# maplemini.net
KiCad netlist of a schematic drawn in EAGLE
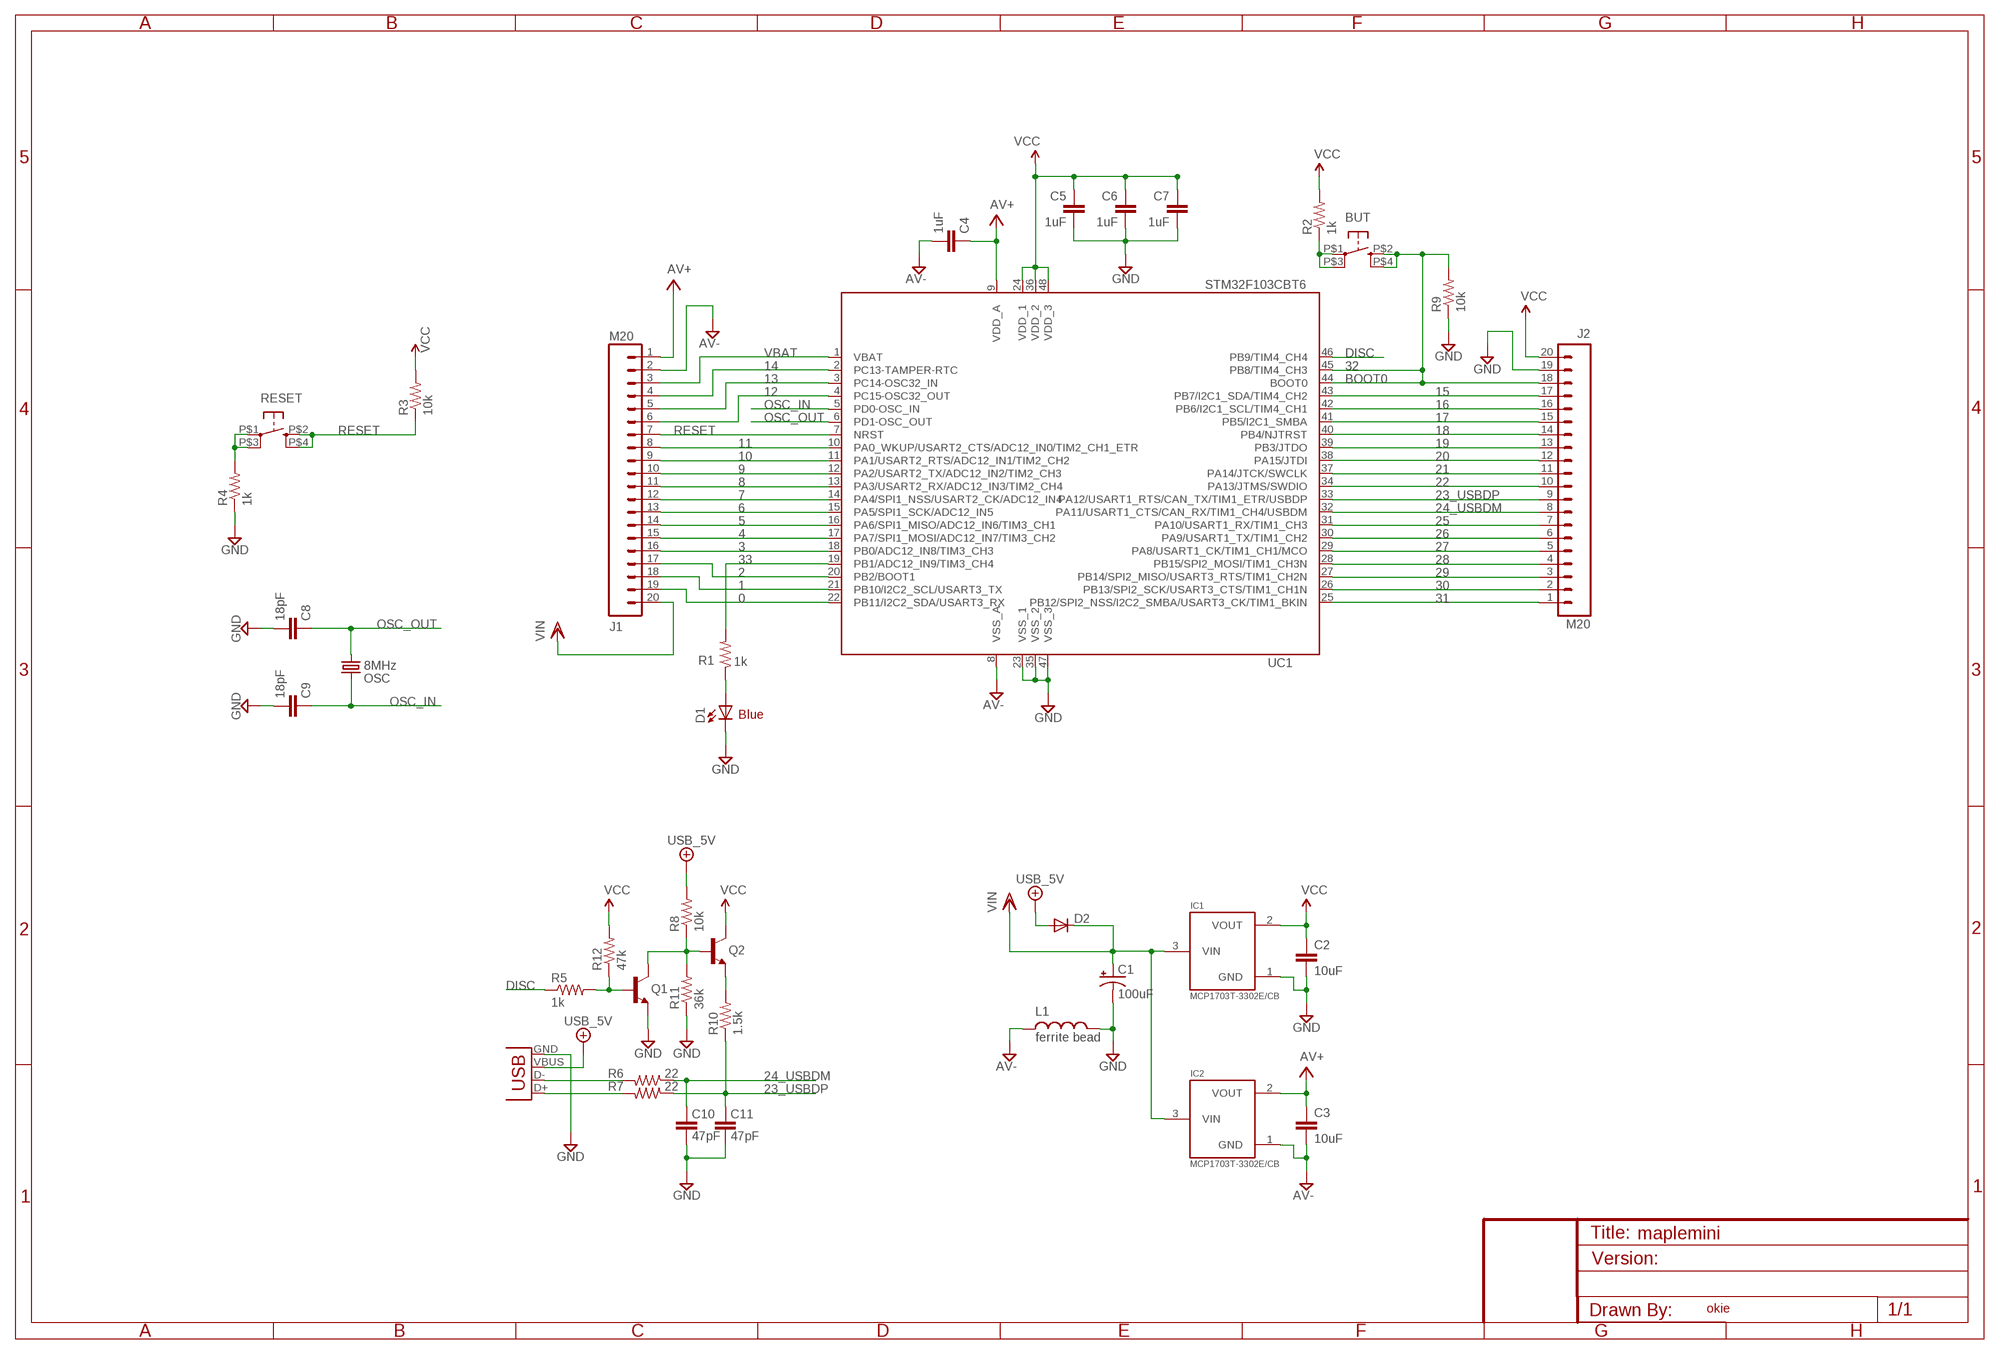
[diagram p0: schematic, sheet 1]

(export (version "E")
  (design (tool "Eeschema 10.0.6"))
  (components
    (comp (ref "BUT")
      (value "KMR211GLFS")
      (footprint "eagle-import:PUSHBUTTON-KMR241GLFS")
      (libsource (lib "eagle-import") (part "BUTTON-KMR241GLFS"))
    )
    (comp (ref "C1")
      (value "100uF")
      (footprint "eagle-import:EIA3216")
      (libsource (lib "eagle-import") (part "CAP_POL1206"))
    )
    (comp (ref "C2")
      (value "10uF")
      (footprint "eagle-import:0805")
      (libsource (lib "eagle-import") (part "SparkFun2_CAP0805"))
    )
    (comp (ref "C3")
      (value "10uF")
      (footprint "eagle-import:0805")
      (libsource (lib "eagle-import") (part "SparkFun2_CAP0805"))
    )
    (comp (ref "C4")
      (value "1uF")
      (footprint "eagle-import:C0402")
      (libsource (lib "eagle-import") (part "CAP0402"))
    )
    (comp (ref "C5")
      (value "1uF")
      (footprint "eagle-import:C0402")
      (libsource (lib "eagle-import") (part "CAP0402"))
    )
    (comp (ref "C6")
      (value "1uF")
      (footprint "eagle-import:C0402")
      (libsource (lib "eagle-import") (part "CAP0402"))
    )
    (comp (ref "C7")
      (value "1uF")
      (footprint "eagle-import:C0402")
      (libsource (lib "eagle-import") (part "CAP0402"))
    )
    (comp (ref "C8")
      (value "18pF")
      (footprint "eagle-import:C0402")
      (libsource (lib "eagle-import") (part "CAP0402"))
    )
    (comp (ref "C9")
      (value "18pF")
      (footprint "eagle-import:C0402")
      (libsource (lib "eagle-import") (part "CAP0402"))
    )
    (comp (ref "C10")
      (value "47pF")
      (footprint "eagle-import:C0402")
      (libsource (lib "eagle-import") (part "CAP0402"))
    )
    (comp (ref "C11")
      (value "47pF")
      (footprint "eagle-import:C0402")
      (libsource (lib "eagle-import") (part "CAP0402"))
    )
    (comp (ref "D1")
      (value "Blue")
      (footprint "eagle-import:LED-1206")
      (libsource (lib "eagle-import") (part "LED1206"))
    )
    (comp (ref "D2")
      (value "DIODESOD")
      (footprint "eagle-import:SOD-323")
      (libsource (lib "eagle-import") (part "DIODESOD"))
    )
    (comp (ref "IC1")
      (value "MCP1703T-3302E/CB")
      (footprint "eagle-import:SOT23")
      (libsource (lib "eagle-import") (part "MCP1700T"))
    )
    (comp (ref "IC2")
      (value "MCP1703T-3302E/CB")
      (footprint "eagle-import:SOT23")
      (libsource (lib "eagle-import") (part "MCP1700T"))
    )
    (comp (ref "J1")
      (value "M20")
      (footprint "eagle-import:1X20")
      (libsource (lib "eagle-import") (part "M20"))
    )
    (comp (ref "J2")
      (value "M20")
      (footprint "eagle-import:1X20")
      (libsource (lib "eagle-import") (part "M20"))
    )
    (comp (ref "L1")
      (value "ferrite bead")
      (footprint "eagle-import:0603")
      (libsource (lib "eagle-import") (part "INDUCTOR0603"))
    )
    (comp (ref "OSC")
      (value "8MHz")
      (footprint "eagle-import:CRYSTAL-SMD-5X3")
      (libsource (lib "eagle-import") (part "CRYSTAL5X3"))
    )
    (comp (ref "Q1")
      (value "NPN-BJT")
      (footprint "eagle-import:SOT23")
      (libsource (lib "eagle-import") (part "TRANSISTOR_NPNSOT23"))
    )
    (comp (ref "Q2")
      (value "NPN-BJT")
      (footprint "eagle-import:SOT23")
      (libsource (lib "eagle-import") (part "TRANSISTOR_NPNSOT23"))
    )
    (comp (ref "R1")
      (value "1k")
      (footprint "eagle-import:C0402")
      (libsource (lib "eagle-import") (part "RESISTOR0402"))
    )
    (comp (ref "R2")
      (value "1k")
      (footprint "eagle-import:C0402")
      (libsource (lib "eagle-import") (part "RESISTOR0402"))
    )
    (comp (ref "R3")
      (value "10k")
      (footprint "eagle-import:C0402")
      (libsource (lib "eagle-import") (part "RESISTOR0402"))
    )
    (comp (ref "R4")
      (value "1k")
      (footprint "eagle-import:C0402")
      (libsource (lib "eagle-import") (part "RESISTOR0402"))
    )
    (comp (ref "R5")
      (value "1k")
      (footprint "eagle-import:C0402")
      (libsource (lib "eagle-import") (part "RESISTOR0402"))
    )
    (comp (ref "R6")
      (value "22")
      (footprint "eagle-import:C0402")
      (libsource (lib "eagle-import") (part "RESISTOR0402"))
    )
    (comp (ref "R7")
      (value "22")
      (footprint "eagle-import:C0402")
      (libsource (lib "eagle-import") (part "RESISTOR0402"))
    )
    (comp (ref "R8")
      (value "10k")
      (footprint "eagle-import:C0402")
      (libsource (lib "eagle-import") (part "RESISTOR0402"))
    )
    (comp (ref "R9")
      (value "10k")
      (footprint "eagle-import:C0402")
      (libsource (lib "eagle-import") (part "RESISTOR0402"))
    )
    (comp (ref "R10")
      (value "1.5k")
      (footprint "eagle-import:C0402")
      (libsource (lib "eagle-import") (part "RESISTOR0402"))
    )
    (comp (ref "R11")
      (value "36k")
      (footprint "eagle-import:C0402")
      (libsource (lib "eagle-import") (part "RESISTOR0402"))
    )
    (comp (ref "R12")
      (value "47k")
      (footprint "eagle-import:C0402")
      (libsource (lib "eagle-import") (part "RESISTOR0402"))
    )
    (comp (ref "RESET")
      (value "KMR211GLFS")
      (footprint "eagle-import:PUSHBUTTON-KMR241GLFS")
      (libsource (lib "eagle-import") (part "BUTTON-KMR241GLFS"))
    )
    (comp (ref "UC1")
      (value "STM32F103CBT6")
      (footprint "eagle-import:LQFP48")
      (libsource (lib "eagle-import") (part "STM32F103CB"))
    )
    (comp (ref "X1")
      (value "USB-MINIB")
      (footprint "eagle-import:USB-MINIB")
      (libsource (lib "eagle-import") (part "USBSMD"))
    )
  )
  (nets
    (net (code "1") (name "/0") (class "Default")
      (node (ref "J1") (pin "19") (pinfunction "19_19") (pintype "passive"))
      (node (ref "UC1") (pin "22") (pinfunction "PB11/I2C2_SDA/USART3_RX_22") (pintype "input"))
    )
    (net (code "2") (name "/1") (class "Default")
      (node (ref "J1") (pin "18") (pinfunction "18_18") (pintype "passive"))
      (node (ref "UC1") (pin "21") (pinfunction "PB10/I2C2_SCL/USART3_TX_21") (pintype "input"))
    )
    (net (code "3") (name "/2") (class "Default")
      (node (ref "J1") (pin "17") (pinfunction "17_17") (pintype "passive"))
      (node (ref "UC1") (pin "20") (pinfunction "PB2/BOOT1_20") (pintype "bidirectional"))
    )
    (net (code "4") (name "/3") (class "Default")
      (node (ref "J1") (pin "16") (pinfunction "16_16") (pintype "passive"))
      (node (ref "UC1") (pin "18") (pinfunction "PB0/ADC12_IN8/TIM3_CH3_18") (pintype "bidirectional"))
    )
    (net (code "5") (name "/4") (class "Default")
      (node (ref "J1") (pin "15") (pinfunction "15_15") (pintype "passive"))
      (node (ref "UC1") (pin "17") (pinfunction "PA7/SPI1_MOSI/ADC12_IN7/TIM3_CH2_17") (pintype "bidirectional"))
    )
    (net (code "6") (name "/5") (class "Default")
      (node (ref "J1") (pin "14") (pinfunction "14_14") (pintype "passive"))
      (node (ref "UC1") (pin "16") (pinfunction "PA6/SPI1_MISO/ADC12_IN6/TIM3_CH1_16") (pintype "bidirectional"))
    )
    (net (code "7") (name "/6") (class "Default")
      (node (ref "J1") (pin "13") (pinfunction "13_13") (pintype "passive"))
      (node (ref "UC1") (pin "15") (pinfunction "PA5/SPI1_SCK/ADC12_IN5_15") (pintype "bidirectional"))
    )
    (net (code "8") (name "/7") (class "Default")
      (node (ref "J1") (pin "12") (pinfunction "12_12") (pintype "passive"))
      (node (ref "UC1") (pin "14") (pinfunction "PA4/SPI1_NSS/USART2_CK/ADC12_IN4_14") (pintype "bidirectional"))
    )
    (net (code "9") (name "/8") (class "Default")
      (node (ref "J1") (pin "11") (pinfunction "11_11") (pintype "passive"))
      (node (ref "UC1") (pin "13") (pinfunction "PA3/USART2_RX/ADC12_IN3/TIM2_CH4_13") (pintype "bidirectional"))
    )
    (net (code "10") (name "/9") (class "Default")
      (node (ref "J1") (pin "10") (pinfunction "10_10") (pintype "passive"))
      (node (ref "UC1") (pin "12") (pinfunction "PA2/USART2_TX/ADC12_IN2/TIM2_CH3_12") (pintype "bidirectional"))
    )
    (net (code "11") (name "/10") (class "Default")
      (node (ref "J1") (pin "9") (pinfunction "9_9") (pintype "passive"))
      (node (ref "UC1") (pin "11") (pinfunction "PA1/USART2_RTS/ADC12_IN1/TIM2_CH2_11") (pintype "bidirectional"))
    )
    (net (code "12") (name "/11") (class "Default")
      (node (ref "J1") (pin "8") (pinfunction "8_8") (pintype "passive"))
      (node (ref "UC1") (pin "10") (pinfunction "PA0_WKUP/USART2_CTS/ADC12_IN0/TIM2_CH1_ETR_10") (pintype "bidirectional"))
    )
    (net (code "13") (name "/12") (class "Default")
      (node (ref "J1") (pin "6") (pinfunction "6_6") (pintype "passive"))
      (node (ref "UC1") (pin "4") (pinfunction "PC15-OSC32_OUT_4") (pintype "input"))
    )
    (net (code "14") (name "/13") (class "Default")
      (node (ref "J1") (pin "5") (pinfunction "5_5") (pintype "passive"))
      (node (ref "UC1") (pin "3") (pinfunction "PC14-OSC32_IN_3") (pintype "input"))
    )
    (net (code "15") (name "/14") (class "Default")
      (node (ref "J1") (pin "4") (pinfunction "4_4") (pintype "passive"))
      (node (ref "UC1") (pin "2") (pinfunction "PC13-TAMPER-RTC_2") (pintype "input"))
    )
    (net (code "16") (name "/15") (class "Default")
      (node (ref "J2") (pin "17") (pinfunction "17_17") (pintype "passive"))
      (node (ref "UC1") (pin "43") (pinfunction "PB7/I2C1_SDA/TIM4_CH2_43") (pintype "bidirectional"))
    )
    (net (code "17") (name "/16") (class "Default")
      (node (ref "J2") (pin "16") (pinfunction "16_16") (pintype "passive"))
      (node (ref "UC1") (pin "42") (pinfunction "PB6/I2C1_SCL/TIM4_CH1_42") (pintype "input"))
    )
    (net (code "18") (name "/17") (class "Default")
      (node (ref "J2") (pin "15") (pinfunction "15_15") (pintype "passive"))
      (node (ref "UC1") (pin "41") (pinfunction "PB5/I2C1_SMBA_41") (pintype "input"))
    )
    (net (code "19") (name "/18") (class "Default")
      (node (ref "J2") (pin "14") (pinfunction "14_14") (pintype "passive"))
      (node (ref "UC1") (pin "40") (pinfunction "PB4/NJTRST_40") (pintype "bidirectional"))
    )
    (net (code "20") (name "/19") (class "Default")
      (node (ref "J2") (pin "13") (pinfunction "13_13") (pintype "passive"))
      (node (ref "UC1") (pin "39") (pinfunction "PB3/JTDO_39") (pintype "bidirectional"))
    )
    (net (code "21") (name "/20") (class "Default")
      (node (ref "J2") (pin "12") (pinfunction "12_12") (pintype "passive"))
      (node (ref "UC1") (pin "38") (pinfunction "PA15/JTDI_38") (pintype "bidirectional"))
    )
    (net (code "22") (name "/21") (class "Default")
      (node (ref "J2") (pin "11") (pinfunction "11_11") (pintype "passive"))
      (node (ref "UC1") (pin "37") (pinfunction "PA14/JTCK/SWCLK_37") (pintype "bidirectional"))
    )
    (net (code "23") (name "/22") (class "Default")
      (node (ref "J2") (pin "10") (pinfunction "10_10") (pintype "passive"))
      (node (ref "UC1") (pin "34") (pinfunction "PA13/JTMS/SWDIO_34") (pintype "bidirectional"))
    )
    (net (code "24") (name "/23_USBDP") (class "Default")
      (node (ref "C11") (pin "2") (pinfunction "2_2") (pintype "passive"))
      (node (ref "J2") (pin "9") (pinfunction "9_9") (pintype "passive"))
      (node (ref "R10") (pin "1") (pinfunction "1_1") (pintype "passive"))
      (node (ref "R7") (pin "1") (pinfunction "1_1") (pintype "passive"))
      (node (ref "UC1") (pin "33") (pinfunction "PA12/USART1_RTS/CAN_TX/TIM1_ETR/USBDP_33") (pintype "bidirectional"))
    )
    (net (code "25") (name "/24_USBDM") (class "Default")
      (node (ref "C10") (pin "2") (pinfunction "2_2") (pintype "passive"))
      (node (ref "J2") (pin "8") (pinfunction "8_8") (pintype "passive"))
      (node (ref "R6") (pin "1") (pinfunction "1_1") (pintype "passive"))
      (node (ref "UC1") (pin "32") (pinfunction "PA11/USART1_CTS/CAN_RX/TIM1_CH4/USBDM_32") (pintype "bidirectional"))
    )
    (net (code "26") (name "/25") (class "Default")
      (node (ref "J2") (pin "7") (pinfunction "7_7") (pintype "passive"))
      (node (ref "UC1") (pin "31") (pinfunction "PA10/USART1_RX/TIM1_CH3_31") (pintype "bidirectional"))
    )
    (net (code "27") (name "/26") (class "Default")
      (node (ref "J2") (pin "6") (pinfunction "6_6") (pintype "passive"))
      (node (ref "UC1") (pin "30") (pinfunction "PA9/USART1_TX/TIM1_CH2_30") (pintype "input"))
    )
    (net (code "28") (name "/27") (class "Default")
      (node (ref "J2") (pin "5") (pinfunction "5_5") (pintype "passive"))
      (node (ref "UC1") (pin "29") (pinfunction "PA8/USART1_CK/TIM1_CH1/MCO_29") (pintype "bidirectional"))
    )
    (net (code "29") (name "/28") (class "Default")
      (node (ref "J2") (pin "4") (pinfunction "4_4") (pintype "passive"))
      (node (ref "UC1") (pin "28") (pinfunction "PB15/SPI2_MOSI/TIM1_CH3N_28") (pintype "input"))
    )
    (net (code "30") (name "/29") (class "Default")
      (node (ref "J2") (pin "3") (pinfunction "3_3") (pintype "passive"))
      (node (ref "UC1") (pin "27") (pinfunction "PB14/SPI2_MISO/USART3_RTS/TIM1_CH2N_27") (pintype "input"))
    )
    (net (code "31") (name "/30") (class "Default")
      (node (ref "J2") (pin "2") (pinfunction "2_2") (pintype "passive"))
      (node (ref "UC1") (pin "26") (pinfunction "PB13/SPI2_SCK/USART3_CTS/TIM1_CH1N_26") (pintype "input"))
    )
    (net (code "32") (name "/31") (class "Default")
      (node (ref "J2") (pin "1") (pinfunction "1_1") (pintype "passive"))
      (node (ref "UC1") (pin "25") (pinfunction "PB12/SPI2_NSS/I2C2_SMBA/USART3_CK/TIM1_BKIN_25") (pintype "input"))
    )
    (net (code "33") (name "/32") (class "Default")
      (node (ref "BUT") (pin "P$2") (pinfunction "2_P$2") (pintype "passive"))
      (node (ref "BUT") (pin "P$4") (pinfunction "4_P$4") (pintype "passive"))
      (node (ref "J2") (pin "18") (pinfunction "18_18") (pintype "passive"))
      (node (ref "R9") (pin "2") (pinfunction "2_2") (pintype "passive"))
      (node (ref "UC1") (pin "44") (pinfunction "BOOT0_44") (pintype "input"))
      (node (ref "UC1") (pin "45") (pinfunction "PB8/TIM4_CH3_45") (pintype "bidirectional"))
    )
    (net (code "34") (name "/33") (class "Default")
      (node (ref "R1") (pin "2") (pinfunction "2_2") (pintype "passive"))
      (node (ref "UC1") (pin "19") (pinfunction "PB1/ADC12_IN9/TIM3_CH4_19") (pintype "bidirectional"))
    )
    (net (code "35") (name "/DISC") (class "Default")
      (node (ref "R5") (pin "1") (pinfunction "1_1") (pintype "passive"))
      (node (ref "UC1") (pin "46") (pinfunction "PB9/TIM4_CH4_46") (pintype "input"))
    )
    (net (code "36") (name "/OSC_IN") (class "Default")
      (node (ref "C9") (pin "1") (pinfunction "1_1") (pintype "passive"))
      (node (ref "OSC") (pin "3") (pinfunction "2_3") (pintype "passive"))
      (node (ref "UC1") (pin "5") (pinfunction "PD0-OSC_IN_5") (pintype "input"))
    )
    (net (code "37") (name "/OSC_OUT") (class "Default")
      (node (ref "C8") (pin "1") (pinfunction "1_1") (pintype "passive"))
      (node (ref "OSC") (pin "1") (pinfunction "1_1") (pintype "passive"))
      (node (ref "UC1") (pin "6") (pinfunction "PD1-OSC_OUT_6") (pintype "input"))
    )
    (net (code "38") (name "/RESET") (class "Default")
      (node (ref "J1") (pin "7") (pinfunction "7_7") (pintype "passive"))
      (node (ref "R3") (pin "1") (pinfunction "1_1") (pintype "passive"))
      (node (ref "RESET") (pin "P$2") (pinfunction "2_P$2") (pintype "passive"))
      (node (ref "RESET") (pin "P$4") (pinfunction "4_P$4") (pintype "passive"))
      (node (ref "UC1") (pin "7") (pinfunction "NRST_7") (pintype "input"))
    )
    (net (code "39") (name "/VBAT") (class "Default")
      (node (ref "J1") (pin "3") (pinfunction "3_3") (pintype "passive"))
      (node (ref "UC1") (pin "1") (pinfunction "VBAT_1") (pintype "power_in"))
    )
    (net (code "40") (name "AV+") (class "Default")
      (node (ref "C3") (pin "1") (pinfunction "1_1") (pintype "passive"))
      (node (ref "C4") (pin "1") (pinfunction "1_1") (pintype "passive"))
      (node (ref "IC2") (pin "2") (pinfunction "VOUT_2") (pintype "bidirectional"))
      (node (ref "J1") (pin "1") (pinfunction "1_1") (pintype "passive"))
      (node (ref "UC1") (pin "9") (pinfunction "VDD_A_9") (pintype "power_in"))
    )
    (net (code "41") (name "AV-") (class "Default")
      (node (ref "C3") (pin "2") (pinfunction "2_2") (pintype "passive"))
      (node (ref "C4") (pin "2") (pinfunction "2_2") (pintype "passive"))
      (node (ref "IC2") (pin "1") (pinfunction "GND_1") (pintype "bidirectional"))
      (node (ref "J1") (pin "2") (pinfunction "2_2") (pintype "passive"))
      (node (ref "L1") (pin "1") (pinfunction "1_1") (pintype "passive"))
      (node (ref "UC1") (pin "8") (pinfunction "VSS_A_8") (pintype "power_in"))
    )
    (net (code "42") (name "GND") (class "Default")
      (node (ref "C1") (pin "C") (pinfunction "-_C") (pintype "passive"))
      (node (ref "C10") (pin "1") (pinfunction "1_1") (pintype "passive"))
      (node (ref "C11") (pin "1") (pinfunction "1_1") (pintype "passive"))
      (node (ref "C2") (pin "2") (pinfunction "2_2") (pintype "passive"))
      (node (ref "C5") (pin "2") (pinfunction "2_2") (pintype "passive"))
      (node (ref "C6") (pin "2") (pinfunction "2_2") (pintype "passive"))
      (node (ref "C7") (pin "2") (pinfunction "2_2") (pintype "passive"))
      (node (ref "C8") (pin "2") (pinfunction "2_2") (pintype "passive"))
      (node (ref "C9") (pin "2") (pinfunction "2_2") (pintype "passive"))
      (node (ref "D1") (pin "C") (pinfunction "C_C") (pintype "passive"))
      (node (ref "IC1") (pin "1") (pinfunction "GND_1") (pintype "bidirectional"))
      (node (ref "J2") (pin "19") (pinfunction "19_19") (pintype "passive"))
      (node (ref "L1") (pin "2") (pinfunction "2_2") (pintype "passive"))
      (node (ref "Q1") (pin "2") (pinfunction "E_2") (pintype "passive"))
      (node (ref "R11") (pin "1") (pinfunction "1_1") (pintype "passive"))
      (node (ref "R4") (pin "1") (pinfunction "1_1") (pintype "passive"))
      (node (ref "R9") (pin "1") (pinfunction "1_1") (pintype "passive"))
      (node (ref "UC1") (pin "23") (pinfunction "VSS_1_23") (pintype "power_in"))
      (node (ref "UC1") (pin "35") (pinfunction "VSS_2_35") (pintype "power_in"))
      (node (ref "UC1") (pin "47") (pinfunction "VSS_3_47") (pintype "power_in"))
      (node (ref "X1") (pin "GND") (pinfunction "GND_GND") (pintype "bidirectional"))
    )
    (net (code "43") (name "Net-(BUT-1)") (class "Default")
      (node (ref "BUT") (pin "P$1") (pinfunction "1_P$1") (pintype "passive"))
      (node (ref "BUT") (pin "P$3") (pinfunction "3_P$3") (pintype "passive"))
      (node (ref "R2") (pin "1") (pinfunction "1_1") (pintype "passive"))
    )
    (net (code "44") (name "Net-(D1-PadA)") (class "Default")
      (node (ref "D1") (pin "A") (pinfunction "A_A") (pintype "passive"))
      (node (ref "R1") (pin "1") (pinfunction "1_1") (pintype "passive"))
    )
    (net (code "45") (name "Net-(Q1-B)") (class "Default")
      (node (ref "Q1") (pin "1") (pinfunction "B_1") (pintype "passive"))
      (node (ref "R12") (pin "1") (pinfunction "1_1") (pintype "passive"))
      (node (ref "R5") (pin "2") (pinfunction "2_2") (pintype "passive"))
    )
    (net (code "46") (name "Net-(Q1-C)") (class "Default")
      (node (ref "Q1") (pin "3") (pinfunction "C_3") (pintype "passive"))
      (node (ref "Q2") (pin "1") (pinfunction "B_1") (pintype "passive"))
      (node (ref "R11") (pin "2") (pinfunction "2_2") (pintype "passive"))
      (node (ref "R8") (pin "1") (pinfunction "1_1") (pintype "passive"))
    )
    (net (code "47") (name "Net-(Q2-E)") (class "Default")
      (node (ref "Q2") (pin "2") (pinfunction "E_2") (pintype "passive"))
      (node (ref "R10") (pin "2") (pinfunction "2_2") (pintype "passive"))
    )
    (net (code "48") (name "Net-(R6-Pad2)") (class "Default")
      (node (ref "R6") (pin "2") (pinfunction "2_2") (pintype "passive"))
      (node (ref "X1") (pin "D-") (pinfunction "D-_D-") (pintype "bidirectional"))
    )
    (net (code "49") (name "Net-(R7-Pad2)") (class "Default")
      (node (ref "R7") (pin "2") (pinfunction "2_2") (pintype "passive"))
      (node (ref "X1") (pin "D+") (pinfunction "D+_D+") (pintype "bidirectional"))
    )
    (net (code "50") (name "Net-(RESET-1)") (class "Default")
      (node (ref "R4") (pin "2") (pinfunction "2_2") (pintype "passive"))
      (node (ref "RESET") (pin "P$1") (pinfunction "1_P$1") (pintype "passive"))
      (node (ref "RESET") (pin "P$3") (pinfunction "3_P$3") (pintype "passive"))
    )
    (net (code "51") (name "USB_5V") (class "Default")
      (node (ref "D2") (pin "2") (pinfunction "A_2") (pintype "passive"))
      (node (ref "R8") (pin "2") (pinfunction "2_2") (pintype "passive"))
      (node (ref "X1") (pin "VBUS") (pinfunction "VBUS_VBUS") (pintype "bidirectional"))
    )
    (net (code "52") (name "VCC") (class "Default")
      (node (ref "C2") (pin "1") (pinfunction "1_1") (pintype "passive"))
      (node (ref "C5") (pin "1") (pinfunction "1_1") (pintype "passive"))
      (node (ref "C6") (pin "1") (pinfunction "1_1") (pintype "passive"))
      (node (ref "C7") (pin "1") (pinfunction "1_1") (pintype "passive"))
      (node (ref "IC1") (pin "2") (pinfunction "VOUT_2") (pintype "bidirectional"))
      (node (ref "J2") (pin "20") (pinfunction "20_20") (pintype "passive"))
      (node (ref "Q2") (pin "3") (pinfunction "C_3") (pintype "passive"))
      (node (ref "R12") (pin "2") (pinfunction "2_2") (pintype "passive"))
      (node (ref "R2") (pin "2") (pinfunction "2_2") (pintype "passive"))
      (node (ref "R3") (pin "2") (pinfunction "2_2") (pintype "passive"))
      (node (ref "UC1") (pin "24") (pinfunction "VDD_1_24") (pintype "power_in"))
      (node (ref "UC1") (pin "36") (pinfunction "VDD_2_36") (pintype "power_in"))
      (node (ref "UC1") (pin "48") (pinfunction "VDD_3_48") (pintype "power_in"))
    )
    (net (code "53") (name "VIN") (class "Default")
      (node (ref "C1") (pin "A") (pinfunction "+_A") (pintype "passive"))
      (node (ref "D2") (pin "1") (pinfunction "C_1") (pintype "passive"))
      (node (ref "IC1") (pin "3") (pinfunction "VIN_3") (pintype "bidirectional"))
      (node (ref "IC2") (pin "3") (pinfunction "VIN_3") (pintype "bidirectional"))
      (node (ref "J1") (pin "20") (pinfunction "20_20") (pintype "passive"))
    )
  )
)
